# trinket-mcp23016.net
KiCad netlist of a schematic drawn in EAGLE
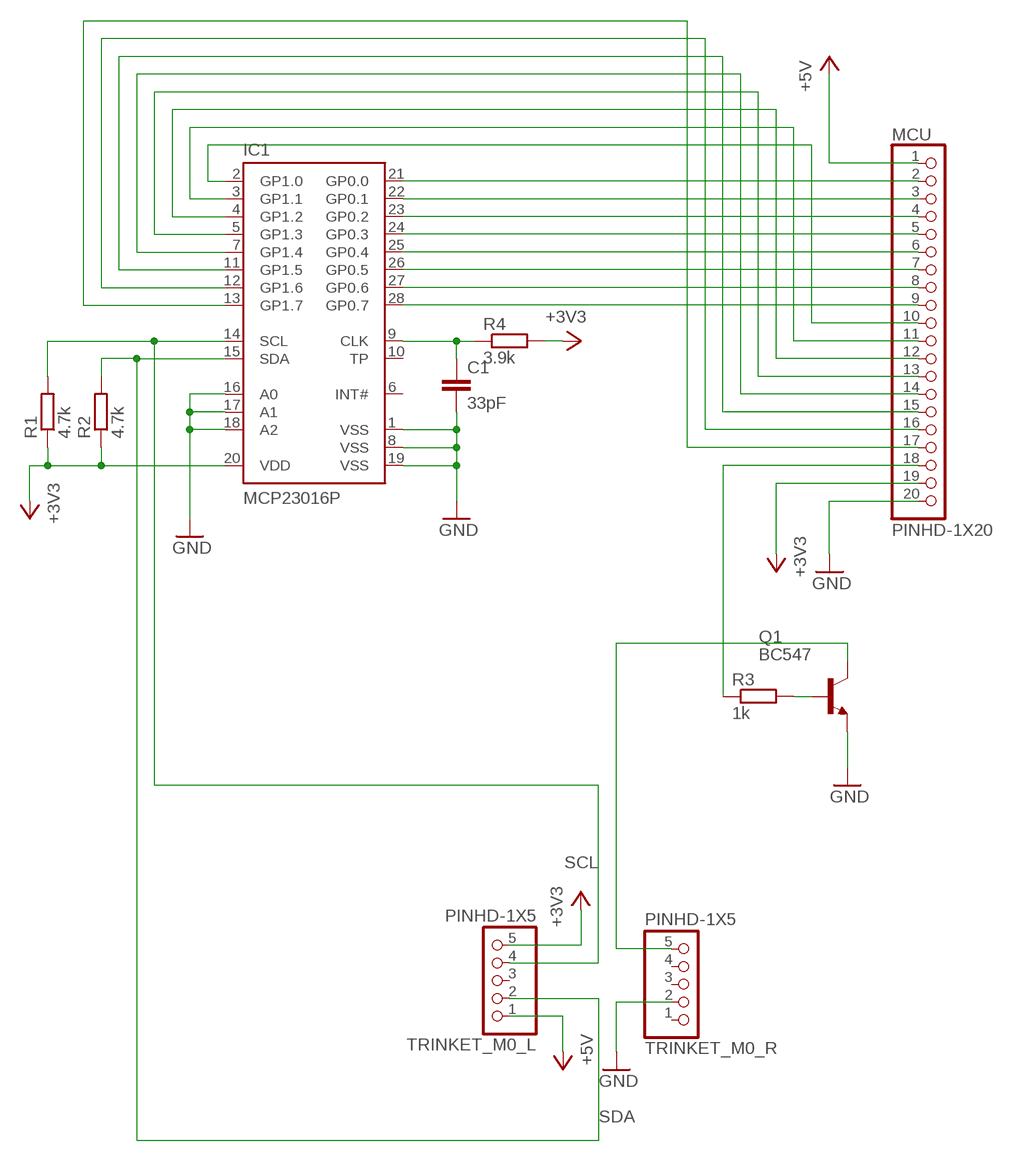
[diagram p0: schematic, sheet 1]

(export (version "E")
  (design (tool "Eeschema 10.0.6"))
  (components
    (comp (ref "C1")
      (value "33pF")
      (footprint "eagle-import:C025-025X050")
      (libsource (lib "eagle-import") (part "C-EU025-025X050"))
    )
    (comp (ref "IC1")
      (value "MCP23016P")
      (footprint "eagle-import:DIL28-3")
      (libsource (lib "eagle-import") (part "MCP23016P"))
    )
    (comp (ref "MCU")
      (value "PINHD-1X20")
      (footprint "eagle-import:1X20")
      (libsource (lib "eagle-import") (part "PINHD-1X20"))
    )
    (comp (ref "Q1")
      (value "BC547")
      (footprint "eagle-import:TO92")
      (libsource (lib "eagle-import") (part "BC547"))
    )
    (comp (ref "R1")
      (value "4.7k")
      (footprint "eagle-import:0207_10")
      (libsource (lib "eagle-import") (part "R-EU_0207/10"))
    )
    (comp (ref "R2")
      (value "4.7k")
      (footprint "eagle-import:0207_10")
      (libsource (lib "eagle-import") (part "R-EU_0207/10"))
    )
    (comp (ref "R3")
      (value "1k")
      (footprint "eagle-import:0207_10")
      (libsource (lib "eagle-import") (part "R-EU_0207/10"))
    )
    (comp (ref "R4")
      (value "3.9k")
      (footprint "eagle-import:0207_10")
      (libsource (lib "eagle-import") (part "R-EU_0207/10"))
    )
    (comp (ref "TRINKET_M0_L")
      (value "PINHD-1X5")
      (footprint "eagle-import:1X05")
      (libsource (lib "eagle-import") (part "PINHD-1X5"))
    )
    (comp (ref "TRINKET_M0_R")
      (value "PINHD-1X5")
      (footprint "eagle-import:1X05")
      (libsource (lib "eagle-import") (part "PINHD-1X5"))
    )
  )
  (nets
    (net (code "1") (name "+3V3") (class "Default")
      (node (ref "IC1") (pin "20") (pinfunction "VDD_20") (pintype "power_in"))
      (node (ref "MCU") (pin "19") (pinfunction "19_19") (pintype "passive"))
      (node (ref "R1") (pin "1") (pinfunction "1_1") (pintype "passive"))
      (node (ref "R2") (pin "1") (pinfunction "1_1") (pintype "passive"))
      (node (ref "R4") (pin "2") (pinfunction "2_2") (pintype "passive"))
      (node (ref "TRINKET_M0_L") (pin "5") (pinfunction "5_5") (pintype "passive"))
    )
    (net (code "2") (name "+5V") (class "Default")
      (node (ref "MCU") (pin "1") (pinfunction "1_1") (pintype "passive"))
      (node (ref "TRINKET_M0_L") (pin "1") (pinfunction "1_1") (pintype "passive"))
    )
    (net (code "3") (name "/SCL") (class "Default")
      (node (ref "IC1") (pin "14") (pinfunction "SCL_14") (pintype "input"))
      (node (ref "R1") (pin "2") (pinfunction "2_2") (pintype "passive"))
      (node (ref "TRINKET_M0_L") (pin "4") (pinfunction "4_4") (pintype "passive"))
    )
    (net (code "4") (name "/SDA") (class "Default")
      (node (ref "IC1") (pin "15") (pinfunction "SDA_15") (pintype "bidirectional"))
      (node (ref "R2") (pin "2") (pinfunction "2_2") (pintype "passive"))
      (node (ref "TRINKET_M0_L") (pin "2") (pinfunction "2_2") (pintype "passive"))
    )
    (net (code "5") (name "GND") (class "Default")
      (node (ref "C1") (pin "2") (pinfunction "2_2") (pintype "passive"))
      (node (ref "IC1") (pin "1") (pinfunction "VSS_1") (pintype "power_in"))
      (node (ref "IC1") (pin "16") (pinfunction "A0_16") (pintype "input"))
      (node (ref "IC1") (pin "17") (pinfunction "A1_17") (pintype "input"))
      (node (ref "IC1") (pin "18") (pinfunction "A2_18") (pintype "input"))
      (node (ref "IC1") (pin "19") (pinfunction "VSS_19") (pintype "power_in"))
      (node (ref "IC1") (pin "8") (pinfunction "VSS_8") (pintype "power_in"))
      (node (ref "MCU") (pin "20") (pinfunction "20_20") (pintype "passive"))
      (node (ref "Q1") (pin "1") (pinfunction "E_1") (pintype "passive"))
      (node (ref "TRINKET_M0_R") (pin "2") (pinfunction "2_2") (pintype "passive"))
    )
    (net (code "6") (name "Net-(IC1-CLK)") (class "Default")
      (node (ref "C1") (pin "1") (pinfunction "1_1") (pintype "passive"))
      (node (ref "IC1") (pin "9") (pinfunction "CLK_9") (pintype "input"))
      (node (ref "R4") (pin "1") (pinfunction "1_1") (pintype "passive"))
    )
    (net (code "7") (name "Net-(IC1-GP0.0)") (class "Default")
      (node (ref "IC1") (pin "21") (pinfunction "GP0.0_21") (pintype "bidirectional"))
      (node (ref "MCU") (pin "2") (pinfunction "2_2") (pintype "passive"))
    )
    (net (code "8") (name "Net-(IC1-GP0.1)") (class "Default")
      (node (ref "IC1") (pin "22") (pinfunction "GP0.1_22") (pintype "bidirectional"))
      (node (ref "MCU") (pin "3") (pinfunction "3_3") (pintype "passive"))
    )
    (net (code "9") (name "Net-(IC1-GP0.2)") (class "Default")
      (node (ref "IC1") (pin "23") (pinfunction "GP0.2_23") (pintype "bidirectional"))
      (node (ref "MCU") (pin "4") (pinfunction "4_4") (pintype "passive"))
    )
    (net (code "10") (name "Net-(IC1-GP0.3)") (class "Default")
      (node (ref "IC1") (pin "24") (pinfunction "GP0.3_24") (pintype "bidirectional"))
      (node (ref "MCU") (pin "5") (pinfunction "5_5") (pintype "passive"))
    )
    (net (code "11") (name "Net-(IC1-GP0.4)") (class "Default")
      (node (ref "IC1") (pin "25") (pinfunction "GP0.4_25") (pintype "bidirectional"))
      (node (ref "MCU") (pin "6") (pinfunction "6_6") (pintype "passive"))
    )
    (net (code "12") (name "Net-(IC1-GP0.5)") (class "Default")
      (node (ref "IC1") (pin "26") (pinfunction "GP0.5_26") (pintype "bidirectional"))
      (node (ref "MCU") (pin "7") (pinfunction "7_7") (pintype "passive"))
    )
    (net (code "13") (name "Net-(IC1-GP0.6)") (class "Default")
      (node (ref "IC1") (pin "27") (pinfunction "GP0.6_27") (pintype "bidirectional"))
      (node (ref "MCU") (pin "8") (pinfunction "8_8") (pintype "passive"))
    )
    (net (code "14") (name "Net-(IC1-GP0.7)") (class "Default")
      (node (ref "IC1") (pin "28") (pinfunction "GP0.7_28") (pintype "bidirectional"))
      (node (ref "MCU") (pin "9") (pinfunction "9_9") (pintype "passive"))
    )
    (net (code "15") (name "Net-(IC1-GP1.0)") (class "Default")
      (node (ref "IC1") (pin "2") (pinfunction "GP1.0_2") (pintype "bidirectional"))
      (node (ref "MCU") (pin "10") (pinfunction "10_10") (pintype "passive"))
    )
    (net (code "16") (name "Net-(IC1-GP1.1)") (class "Default")
      (node (ref "IC1") (pin "3") (pinfunction "GP1.1_3") (pintype "bidirectional"))
      (node (ref "MCU") (pin "11") (pinfunction "11_11") (pintype "passive"))
    )
    (net (code "17") (name "Net-(IC1-GP1.2)") (class "Default")
      (node (ref "IC1") (pin "4") (pinfunction "GP1.2_4") (pintype "bidirectional"))
      (node (ref "MCU") (pin "12") (pinfunction "12_12") (pintype "passive"))
    )
    (net (code "18") (name "Net-(IC1-GP1.3)") (class "Default")
      (node (ref "IC1") (pin "5") (pinfunction "GP1.3_5") (pintype "bidirectional"))
      (node (ref "MCU") (pin "13") (pinfunction "13_13") (pintype "passive"))
    )
    (net (code "19") (name "Net-(IC1-GP1.4)") (class "Default")
      (node (ref "IC1") (pin "7") (pinfunction "GP1.4_7") (pintype "bidirectional"))
      (node (ref "MCU") (pin "14") (pinfunction "14_14") (pintype "passive"))
    )
    (net (code "20") (name "Net-(IC1-GP1.5)") (class "Default")
      (node (ref "IC1") (pin "11") (pinfunction "GP1.5_11") (pintype "bidirectional"))
      (node (ref "MCU") (pin "15") (pinfunction "15_15") (pintype "passive"))
    )
    (net (code "21") (name "Net-(IC1-GP1.6)") (class "Default")
      (node (ref "IC1") (pin "12") (pinfunction "GP1.6_12") (pintype "bidirectional"))
      (node (ref "MCU") (pin "16") (pinfunction "16_16") (pintype "passive"))
    )
    (net (code "22") (name "Net-(IC1-GP1.7)") (class "Default")
      (node (ref "IC1") (pin "13") (pinfunction "GP1.7_13") (pintype "bidirectional"))
      (node (ref "MCU") (pin "17") (pinfunction "17_17") (pintype "passive"))
    )
    (net (code "23") (name "Net-(MCU-Pad18)") (class "Default")
      (node (ref "MCU") (pin "18") (pinfunction "18_18") (pintype "passive"))
      (node (ref "R3") (pin "1") (pinfunction "1_1") (pintype "passive"))
    )
    (net (code "24") (name "Net-(Q1-B)") (class "Default")
      (node (ref "Q1") (pin "2") (pinfunction "B_2") (pintype "passive"))
      (node (ref "R3") (pin "2") (pinfunction "2_2") (pintype "passive"))
    )
    (net (code "25") (name "Net-(Q1-C)") (class "Default")
      (node (ref "Q1") (pin "3") (pinfunction "C_3") (pintype "passive"))
      (node (ref "TRINKET_M0_R") (pin "5") (pinfunction "5_5") (pintype "passive"))
    )
    (net (code "26") (name "unconnected-(IC1-INT#-Pad6)") (class "Default")
      (node (ref "IC1") (pin "6") (pinfunction "INT#_6") (pintype "output"))
    )
    (net (code "27") (name "unconnected-(IC1-TP-Pad10)") (class "Default")
      (node (ref "IC1") (pin "10") (pinfunction "TP_10") (pintype "output"))
    )
    (net (code "28") (name "unconnected-(TRINKET_M0_L-Pad3)") (class "Default")
      (node (ref "TRINKET_M0_L") (pin "3") (pinfunction "3_3") (pintype "passive"))
    )
    (net (code "29") (name "unconnected-(TRINKET_M0_R-Pad1)") (class "Default")
      (node (ref "TRINKET_M0_R") (pin "1") (pinfunction "1_1") (pintype "passive"))
    )
    (net (code "30") (name "unconnected-(TRINKET_M0_R-Pad3)") (class "Default")
      (node (ref "TRINKET_M0_R") (pin "3") (pinfunction "3_3") (pintype "passive"))
    )
    (net (code "31") (name "unconnected-(TRINKET_M0_R-Pad4)") (class "Default")
      (node (ref "TRINKET_M0_R") (pin "4") (pinfunction "4_4") (pintype "passive"))
    )
  )
)
